# ENCODER.net
KiCad netlist of a schematic drawn in Altium Designer
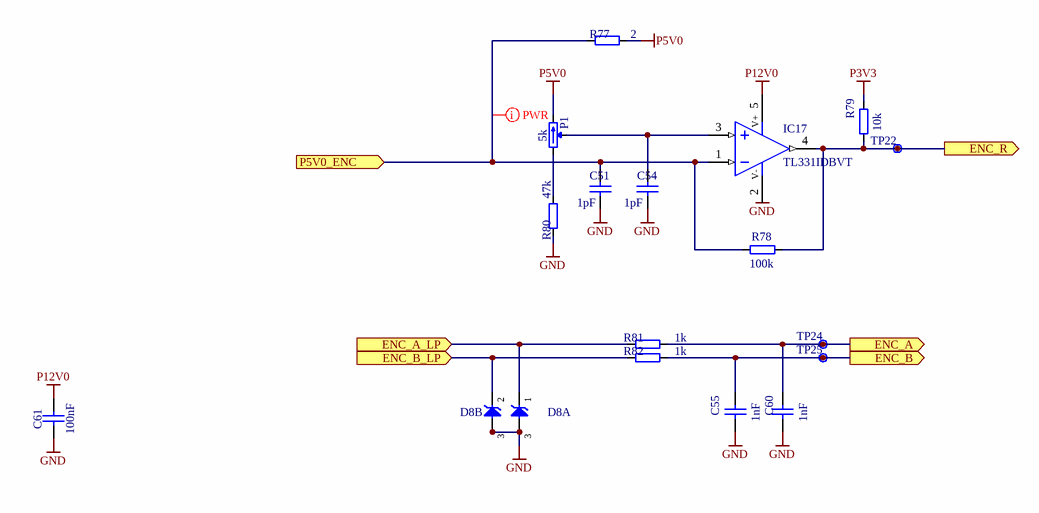
[diagram p0: ENCODER.SchDoc]

(export (version "E")
  (design (tool "Eeschema 10.0.6"))
  (components
    (comp (ref "C51")
      (value "1pF")
      (footprint "CAPC1005X55N")
      (description "Non-polarised capacitor")
      (fields
        (field (name "PART NUMBER") "CC0402_1PF_50V_0.25PF_C0G")
        (field (name "VOLTAGE") "50V")
        (field (name "AUTHOR") "CERN DEM JLC")
      )
      (libsource (lib "Capacitors") (part "Capacitor - non polarized"))
    )
    (comp (ref "C54")
      (value "1pF")
      (footprint "CAPC1005X55N")
      (description "Non-polarised capacitor")
      (fields
        (field (name "PART NUMBER") "CC0402_1PF_50V_0.25PF_C0G")
        (field (name "VOLTAGE") "50V")
        (field (name "AUTHOR") "CERN DEM JLC")
      )
      (libsource (lib "Capacitors") (part "Capacitor - non polarized"))
    )
    (comp (ref "C55")
      (value "1nF")
      (footprint "CAPC1005X55N")
      (description "Non-polarised capacitor")
      (fields
        (field (name "PART NUMBER") "CC0402_1NF_50V_10%_X7R")
        (field (name "VOLTAGE") "50V")
        (field (name "AUTHOR") "CERN DEM JLC")
      )
      (libsource (lib "Capacitors") (part "Capacitor - non polarized"))
    )
    (comp (ref "C60")
      (value "1nF")
      (footprint "CAPC1005X55N")
      (description "Non-polarised capacitor")
      (fields
        (field (name "PART NUMBER") "CC0402_1NF_50V_10%_X7R")
        (field (name "VOLTAGE") "50V")
        (field (name "AUTHOR") "CERN DEM JLC")
      )
      (libsource (lib "Capacitors") (part "Capacitor - non polarized"))
    )
    (comp (ref "C61")
      (value "100nF")
      (footprint "CAPC1005X55N")
      (description "Non-polarised capacitor")
      (fields
        (field (name "PART NUMBER") "CC0402_100NF_16V_10%_X5R")
        (field (name "VOLTAGE") "16V")
        (field (name "AUTHOR") "CERN DEM JLC")
      )
      (libsource (lib "Capacitors") (part "Capacitor - non polarized"))
    )
    (comp (ref "D8")
      (value "ESD5V3U2U-03F")
      (footprint "SOTFL40P120X59-3N")
      (description "Dual Common Anode TVS")
      (fields
        (field (name "VOLTAGE") "5.3V")
        (field (name "MANUFACTURER") "INFINEON")
        (field (name "AUTHOR") "CERN DEM JLC")
      )
      (libsource (lib "ICs And Semiconductors") (part "Diode TVS Uni-Directionnal x2 C1A3_C2A3"))
    )
    (comp (ref "IC17")
      (value "TL331IDBVT")
      (footprint "SOT95P280X145-5N")
      (description "Single Voltage Comparator")
      (fields (field (name "MANUFACTURER") "TEXAS INSTRUMENTS") (field (name "AUTHOR") "CERN DEM JLC"))
      (libsource (lib "ICs And Semiconductors") (part "Operational Amplifier Type13"))
    )
    (comp (ref "P1")
      (value "5k")
      (footprint "TRIM_BOURNS_3314G-1")
      (description "Trimming Potentiometer")
      (fields
        (field (name "PART NUMBER") "TRIM_1T_5K_BOURNS_3314G-1-502E")
        (field (name "POWER") "0.25W")
        (field (name "AUTHOR") "CERN DEM JLC")
      )
      (libsource (lib "Resistors") (part "Trimming Potentiometer"))
    )
    (comp (ref "R77")
      (value "2")
      (footprint "RESC3216X65N")
      (description "Resistor - 1%")
      (fields
        (field (name "PART NUMBER") "R1206_2R_1%_0.25W_200PPM")
        (field (name "POWER") "0.25W")
        (field (name "AUTHOR") "CERN DEM JLC")
      )
      (libsource (lib "Resistors") (part "Resistor - 1%"))
    )
    (comp (ref "R78")
      (value "100k")
      (footprint "RESC1608X55N")
      (description "Resistor - 1%")
      (fields
        (field (name "PART NUMBER") "R0603_100K_1%_0.1W_100PPM")
        (field (name "POWER") "0.1W")
        (field (name "AUTHOR") "CERN DEM JLC")
      )
      (libsource (lib "Resistors") (part "Resistor - 1%"))
    )
    (comp (ref "R79")
      (value "10k")
      (footprint "RESC1005X40N")
      (description "Resistor - 1%")
      (fields
        (field (name "PART NUMBER") "R0402_10K_1%_0.0625W_100PPM")
        (field (name "POWER") "0.0625W")
        (field (name "AUTHOR") "CERN DEM JLC")
      )
      (libsource (lib "Resistors") (part "Resistor - 1%"))
    )
    (comp (ref "R80")
      (value "47k")
      (footprint "RESC1608X55N")
      (description "Resistor - 1%")
      (fields
        (field (name "PART NUMBER") "R0603_47K_1%_0.1W_100PPM")
        (field (name "POWER") "0.1W")
        (field (name "AUTHOR") "CERN DEM JLC")
      )
      (libsource (lib "Resistors") (part "Resistor - 1%"))
    )
    (comp (ref "R81")
      (value "1k")
      (footprint "RESC1005X40N")
      (description "Resistor - 1%")
      (fields
        (field (name "PART NUMBER") "R0402_1K_1%_0.0625W_100PPM")
        (field (name "POWER") "0.0625W")
        (field (name "AUTHOR") "CERN DEM JLC")
      )
      (libsource (lib "Resistors") (part "Resistor - 1%"))
    )
    (comp (ref "R82")
      (value "1k")
      (footprint "RESC1005X40N")
      (description "Resistor - 1%")
      (fields
        (field (name "PART NUMBER") "R0402_1K_1%_0.0625W_100PPM")
        (field (name "POWER") "0.0625W")
        (field (name "AUTHOR") "CERN DEM JLC")
      )
      (libsource (lib "Resistors") (part "Resistor - 1%"))
    )
    (comp (ref "TP22")
      (value "Plated Hole")
      (footprint "c130h60")
      (description "Single Terminal Socket")
      (fields (field (name "PART NUMBER") "PLATED_HOLE0.6_PAD1.3") (field (name "AUTHOR") "CERN DEM MR"))
      (libsource (lib "Eletro-mechanical") (part "Single Terminal Socket"))
    )
    (comp (ref "TP24")
      (value "Plated Hole")
      (footprint "c130h60")
      (description "Single Terminal Socket")
      (fields (field (name "PART NUMBER") "PLATED_HOLE0.6_PAD1.3") (field (name "AUTHOR") "CERN DEM MR"))
      (libsource (lib "Eletro-mechanical") (part "Single Terminal Socket"))
    )
    (comp (ref "TP25")
      (value "Plated Hole")
      (footprint "c130h60")
      (description "Single Terminal Socket")
      (fields (field (name "PART NUMBER") "PLATED_HOLE0.6_PAD1.3") (field (name "AUTHOR") "CERN DEM MR"))
      (libsource (lib "Eletro-mechanical") (part "Single Terminal Socket"))
    )
  )
  (nets
    (net (code "1") (name "/ENC_A") (class "Default")
      (node (ref "C60") (pin "2") (pinfunction "2_2") (pintype "passive"))
      (node (ref "R81") (pin "1") (pinfunction "1_1") (pintype "passive"))
      (node (ref "TP24") (pin "1") (pinfunction "1_1") (pintype "bidirectional"))
    )
    (net (code "2") (name "/ENC_A_LP") (class "Default")
      (node (ref "D8") (pin "1") (pinfunction "C_1") (pintype "passive"))
      (node (ref "R81") (pin "2") (pinfunction "2_2") (pintype "passive"))
    )
    (net (code "3") (name "/ENC_B") (class "Default")
      (node (ref "C55") (pin "2") (pinfunction "2_2") (pintype "passive"))
      (node (ref "R82") (pin "1") (pinfunction "1_1") (pintype "passive"))
      (node (ref "TP25") (pin "1") (pinfunction "1_1") (pintype "bidirectional"))
    )
    (net (code "4") (name "/ENC_B_LP") (class "Default")
      (node (ref "D8") (pin "2") (pinfunction "C_2") (pintype "passive"))
      (node (ref "R82") (pin "2") (pinfunction "2_2") (pintype "passive"))
    )
    (net (code "5") (name "/ENC_R") (class "Default")
      (node (ref "IC17") (pin "4") (pinfunction "OUT_4") (pintype "output"))
      (node (ref "R78") (pin "1") (pinfunction "1_1") (pintype "passive"))
      (node (ref "R79") (pin "1") (pinfunction "1_1") (pintype "passive"))
      (node (ref "TP22") (pin "1") (pinfunction "1_1") (pintype "bidirectional"))
    )
    (net (code "6") (name "/P5V0_ENC") (class "Default")
      (node (ref "C51") (pin "2") (pinfunction "2_2") (pintype "passive"))
      (node (ref "IC17") (pin "1") (pinfunction "IN-_1") (pintype "input"))
      (node (ref "R77") (pin "2") (pinfunction "2_2") (pintype "passive"))
      (node (ref "R78") (pin "2") (pinfunction "2_2") (pintype "passive"))
    )
    (net (code "7") (name "GND") (class "Default")
      (node (ref "C51") (pin "1") (pinfunction "1_1") (pintype "passive"))
      (node (ref "C54") (pin "1") (pinfunction "1_1") (pintype "passive"))
      (node (ref "C55") (pin "1") (pinfunction "1_1") (pintype "passive"))
      (node (ref "C60") (pin "1") (pinfunction "1_1") (pintype "passive"))
      (node (ref "C61") (pin "1") (pinfunction "1_1") (pintype "passive"))
      (node (ref "D8") (pin "3") (pinfunction "COMA_3") (pintype "passive"))
      (node (ref "R80") (pin "1") (pinfunction "1_1") (pintype "passive"))
    )
    (net (code "8") (name "Net-(IC17-IN+)") (class "Default")
      (node (ref "C54") (pin "2") (pinfunction "2_2") (pintype "passive"))
      (node (ref "IC17") (pin "3") (pinfunction "IN+_3") (pintype "input"))
      (node (ref "P1") (pin "2") (pinfunction "W_2") (pintype "passive"))
    )
    (net (code "9") (name "Net-(P1-CCW)") (class "Default")
      (node (ref "P1") (pin "1") (pinfunction "CCW_1") (pintype "passive"))
      (node (ref "R80") (pin "2") (pinfunction "2_2") (pintype "passive"))
    )
    (net (code "10") (name "P3V3") (class "Default")
      (node (ref "R79") (pin "2") (pinfunction "2_2") (pintype "passive"))
    )
    (net (code "11") (name "P5V0") (class "Default")
      (node (ref "P1") (pin "3") (pinfunction "CW_3") (pintype "passive"))
      (node (ref "R77") (pin "1") (pinfunction "1_1") (pintype "passive"))
    )
    (net (code "12") (name "P12V0") (class "Default")
      (node (ref "C61") (pin "2") (pinfunction "2_2") (pintype "passive"))
      (node (ref "IC17") (pin "5") (pinfunction "VS_5") (pintype "power_in"))
    )
    (net (code "13") (name "unconnected-(IC17-GND-Pad2)") (class "Default")
      (node (ref "IC17") (pin "2") (pinfunction "GND_2") (pintype "power_in"))
    )
  )
)
